# lte_cat_m1_shield_sara-r4.net
KiCad netlist of a schematic drawn in EAGLE
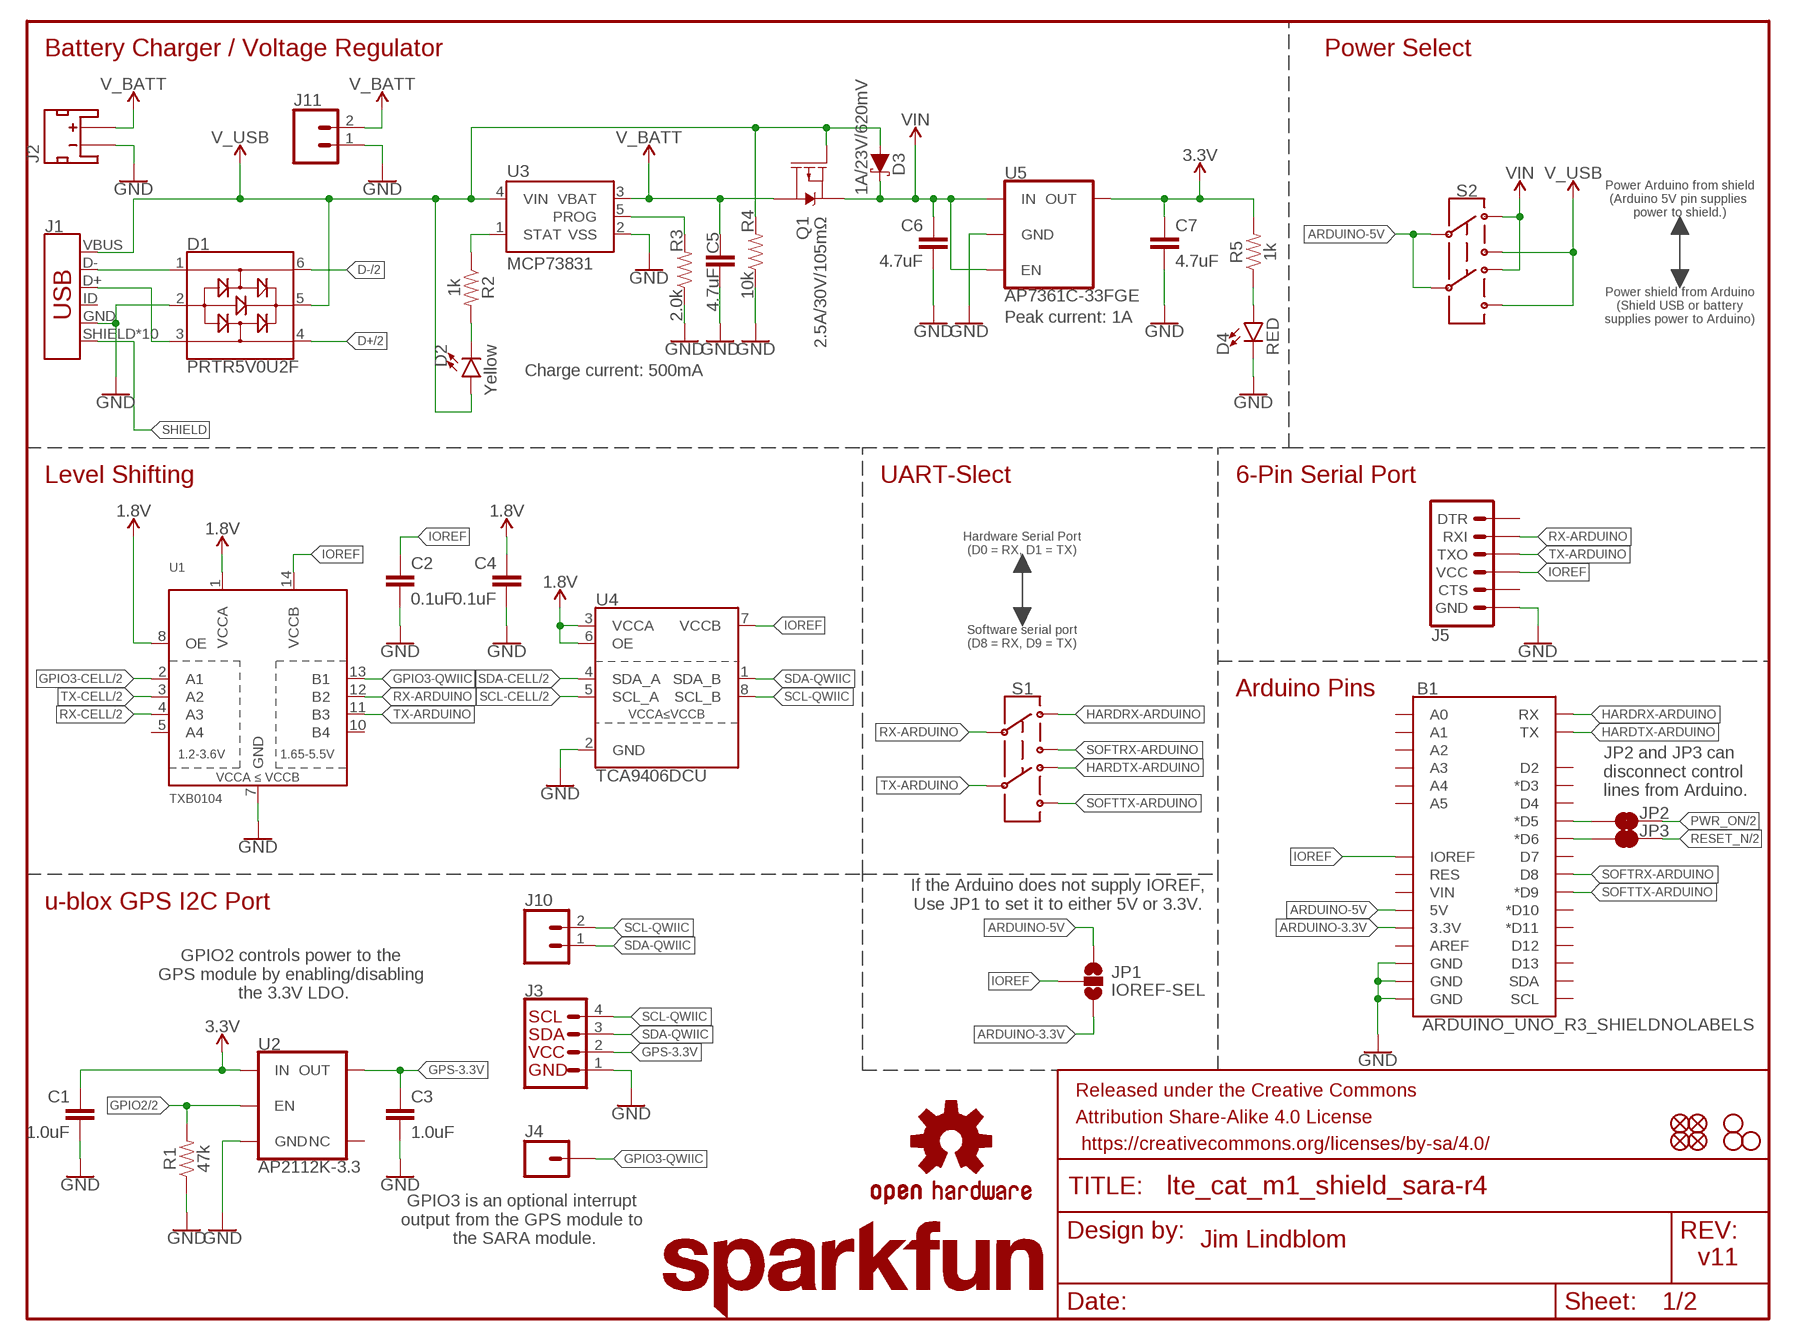
[diagram p0: schematic, sheet 1]
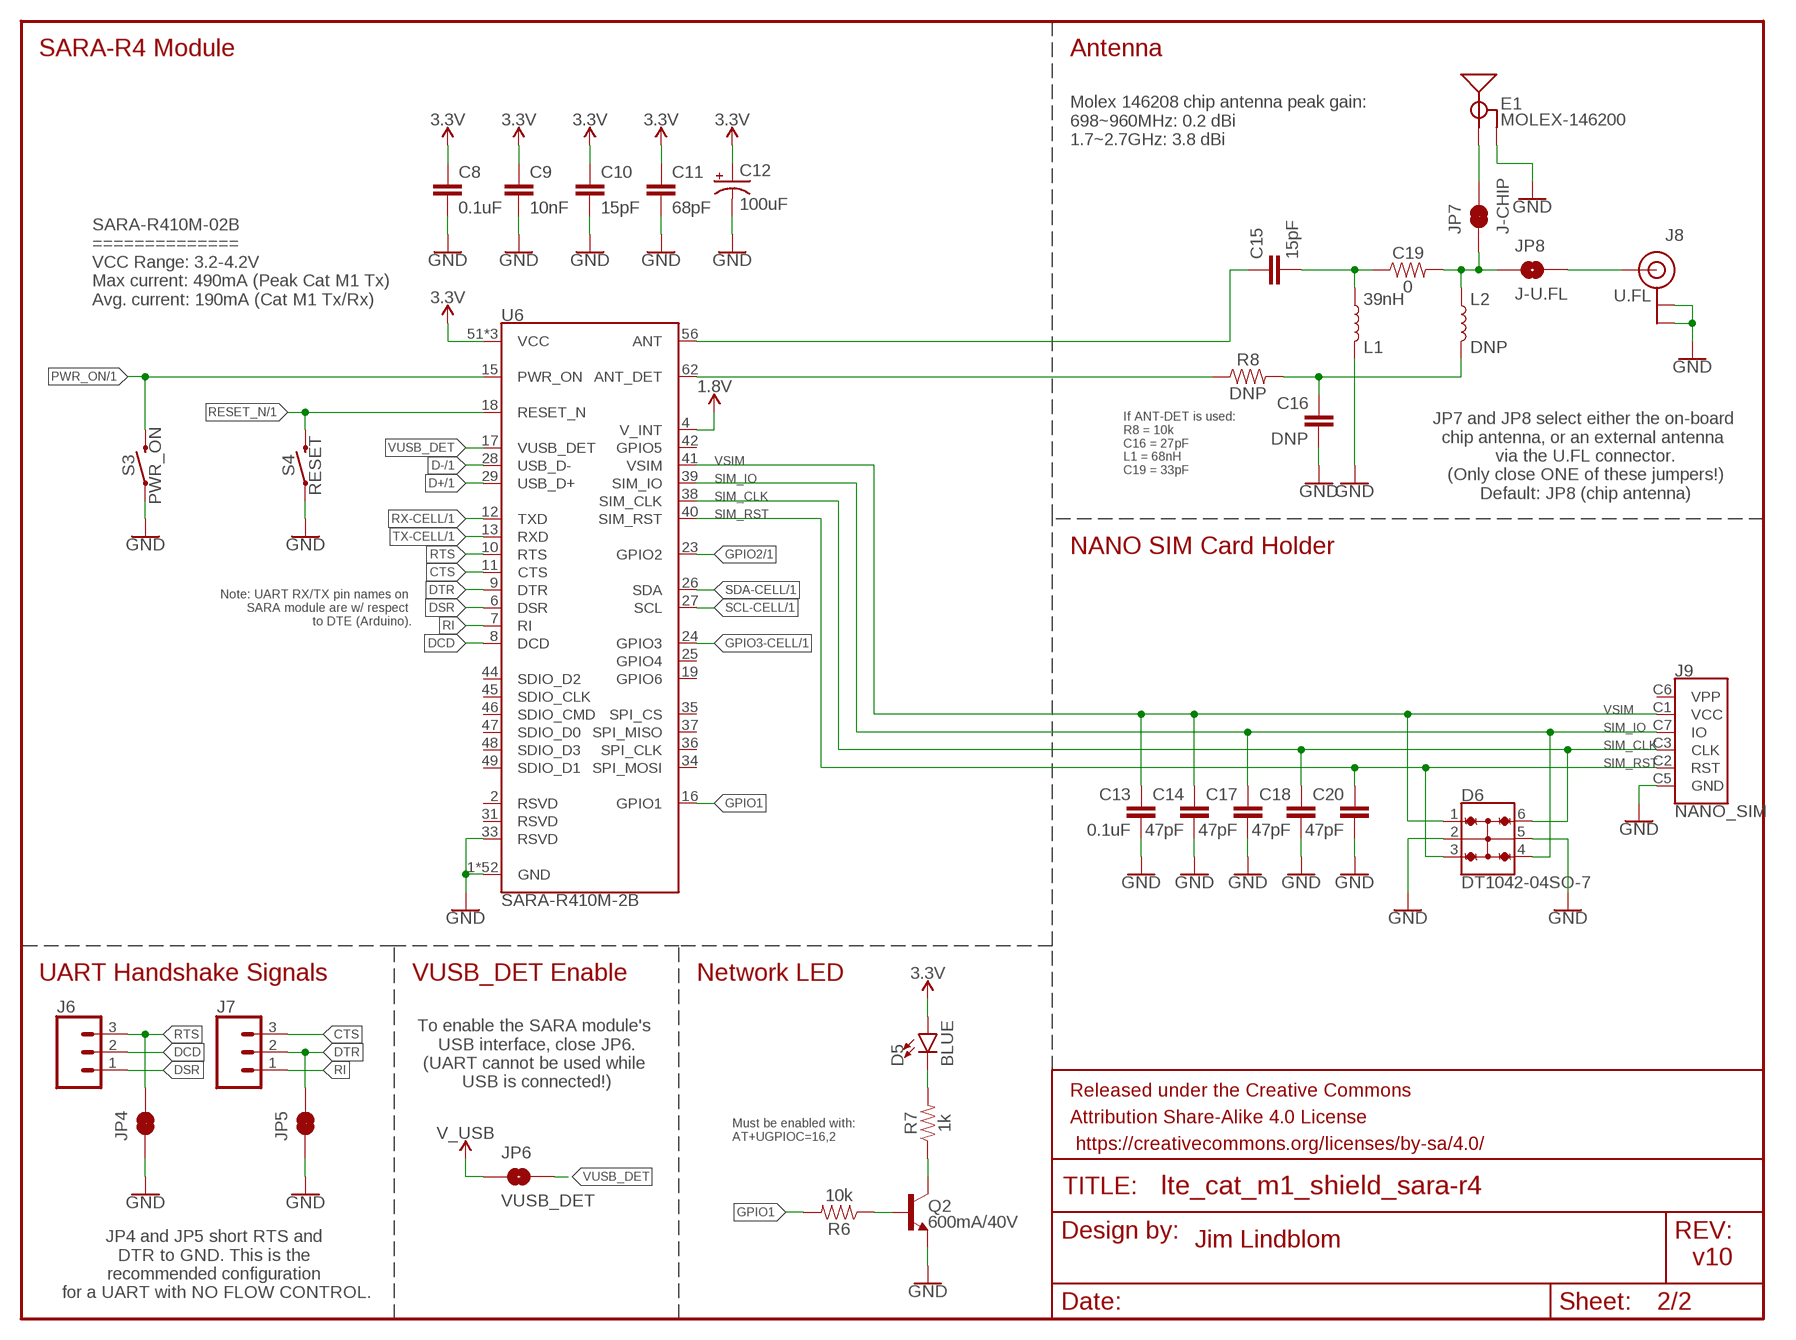
[diagram p1: schematic, sheet 2]

(export (version "E")
  (design (tool "Eeschema 10.0.6"))
  (components
    (comp (ref "B1")
      (value "ARDUINO_UNO_R3_SHIELDNOLABELS")
      (footprint "eagle-import:UNO_R3_SHIELD_NOLABELS")
      (libsource (lib "eagle-import") (part "ARDUINO_UNO_R3_SHIELDNOLABELS"))
    )
    (comp (ref "C1")
      (value "1.0uF")
      (footprint "eagle-import:0603")
      (libsource (lib "eagle-import") (part "1.0UF-0603-16V-10%"))
    )
    (comp (ref "C2")
      (value "0.1uF")
      (footprint "eagle-import:0603")
      (libsource (lib "eagle-import") (part "0.1UF-0603-25V-(+80/-20%)"))
    )
    (comp (ref "C3")
      (value "1.0uF")
      (footprint "eagle-import:0603")
      (libsource (lib "eagle-import") (part "1.0UF-0603-16V-10%"))
    )
    (comp (ref "C4")
      (value "0.1uF")
      (footprint "eagle-import:0603")
      (libsource (lib "eagle-import") (part "0.1UF-0603-25V-(+80/-20%)"))
    )
    (comp (ref "C5")
      (value "4.7uF")
      (footprint "eagle-import:0603")
      (libsource (lib "eagle-import") (part "4.7UF-0603-6.3V-(10%)"))
    )
    (comp (ref "C6")
      (value "4.7uF")
      (footprint "eagle-import:0603")
      (libsource (lib "eagle-import") (part "4.7UF-0603-6.3V-(10%)"))
    )
    (comp (ref "C7")
      (value "4.7uF")
      (footprint "eagle-import:0603")
      (libsource (lib "eagle-import") (part "4.7UF-0603-6.3V-(10%)"))
    )
    (comp (ref "D1")
      (value "PRTR5V0U2F")
      (footprint "eagle-import:SOT886")
      (libsource (lib "eagle-import") (part "PRTR5V0U2F"))
    )
    (comp (ref "D2")
      (value "Yellow")
      (footprint "eagle-import:LED-0603")
      (libsource (lib "eagle-import") (part "LED-YELLOW0603"))
    )
    (comp (ref "D3")
      (value "1A/23V/620mV")
      (footprint "eagle-import:SOD-323")
      (libsource (lib "eagle-import") (part "DIODE-SCHOTTKY-BAT20J"))
    )
    (comp (ref "D4")
      (value "RED")
      (footprint "eagle-import:LED-0603")
      (libsource (lib "eagle-import") (part "LED-RED0603"))
    )
    (comp (ref "FD1")
      (value "FIDUCIALUFIDUCIAL")
      (footprint "eagle-import:FIDUCIAL-MICRO")
      (libsource (lib "eagle-import") (part "FIDUCIALUFIDUCIAL"))
    )
    (comp (ref "FD2")
      (value "FIDUCIALUFIDUCIAL")
      (footprint "eagle-import:FIDUCIAL-MICRO")
      (libsource (lib "eagle-import") (part "FIDUCIALUFIDUCIAL"))
    )
    (comp (ref "FD3")
      (value "FIDUCIALUFIDUCIAL")
      (footprint "eagle-import:FIDUCIAL-MICRO")
      (libsource (lib "eagle-import") (part "FIDUCIALUFIDUCIAL"))
    )
    (comp (ref "FD4")
      (value "FIDUCIALUFIDUCIAL")
      (footprint "eagle-import:FIDUCIAL-MICRO")
      (libsource (lib "eagle-import") (part "FIDUCIALUFIDUCIAL"))
    )
    (comp (ref "FRAME1")
      (value "FRAME-LETTER")
      (footprint "eagle-import:CREATIVE_COMMONS")
      (libsource (lib "eagle-import") (part "FRAME-LETTER"))
    )
    (comp (ref "H1")
      (value "STAND-OFF")
      (footprint "eagle-import:STAND-OFF")
      (libsource (lib "eagle-import") (part "STAND-OFF"))
    )
    (comp (ref "H2")
      (value "STAND-OFF")
      (footprint "eagle-import:STAND-OFF")
      (libsource (lib "eagle-import") (part "STAND-OFF"))
    )
    (comp (ref "H3")
      (value "STAND-OFF")
      (footprint "eagle-import:STAND-OFF")
      (libsource (lib "eagle-import") (part "STAND-OFF"))
    )
    (comp (ref "J1")
      (value "USB_MICRO-B_HALF_PTH_MILL")
      (footprint "eagle-import:USB-MICROB-PTH-MILL")
      (libsource (lib "eagle-import") (part "USB_MICRO-B_HALF_PTH_MILL"))
    )
    (comp (ref "J2")
      (value "JST_2MM_MALESMD")
      (footprint "eagle-import:JST-2-SMD")
      (libsource (lib "eagle-import") (part "JST_2MM_MALESMD"))
    )
    (comp (ref "J3")
      (value "QWIIC_CONNECTORJS-1MM")
      (footprint "eagle-import:1X04_1MM_RA")
      (libsource (lib "eagle-import") (part "QWIIC_CONNECTORJS-1MM"))
    )
    (comp (ref "J4")
      (value "CONN_01PTH_NO_SILK_YES_STOP")
      (footprint "eagle-import:1X01_NO_SILK")
      (libsource (lib "eagle-import") (part "CONN_01PTH_NO_SILK_YES_STOP"))
    )
    (comp (ref "J5")
      (value "6_PIN_SERIAL_TARGETNO_SILK")
      (footprint "eagle-import:1X06_NO_SILK")
      (libsource (lib "eagle-import") (part "6_PIN_SERIAL_TARGETNO_SILK"))
    )
    (comp (ref "J10")
      (value "CONN_021X02_NO_SILK")
      (footprint "eagle-import:1X02_NO_SILK")
      (libsource (lib "eagle-import") (part "CONN_021X02_NO_SILK"))
    )
    (comp (ref "J11")
      (value "CONN_021X02_NO_SILK")
      (footprint "eagle-import:1X02_NO_SILK")
      (libsource (lib "eagle-import") (part "CONN_021X02_NO_SILK"))
    )
    (comp (ref "JP1")
      (value "IOREF-SEL")
      (footprint "eagle-import:SMT-JUMPER_3_NO_SILK")
      (libsource (lib "eagle-import") (part "JUMPER-SMT_3_NO_SILK"))
    )
    (comp (ref "JP2")
      (value "JUMPER-SMT_2_NC_TRACE_SILK")
      (footprint "eagle-import:SMT-JUMPER_2_NC_TRACE_SILK")
      (libsource (lib "eagle-import") (part "JUMPER-SMT_2_NC_TRACE_SILK"))
    )
    (comp (ref "JP3")
      (value "JUMPER-SMT_2_NC_TRACE_SILK")
      (footprint "eagle-import:SMT-JUMPER_2_NC_TRACE_SILK")
      (libsource (lib "eagle-import") (part "JUMPER-SMT_2_NC_TRACE_SILK"))
    )
    (comp (ref "LOGO1")
      (value "SFE_LOGO_NAME.2_INCH")
      (footprint "eagle-import:SFE_LOGO_NAME_.2")
      (libsource (lib "eagle-import") (part "SFE_LOGO_NAME.2_INCH"))
    )
    (comp (ref "LOGO2")
      (value "OSHW-LOGOM")
      (footprint "eagle-import:OSHW-LOGO-M")
      (libsource (lib "eagle-import") (part "OSHW-LOGOM"))
    )
    (comp (ref "LOGO3")
      (value "SFE_LOGO_NAME.2_INCH")
      (footprint "eagle-import:SFE_LOGO_NAME_.2")
      (libsource (lib "eagle-import") (part "SFE_LOGO_NAME.2_INCH"))
    )
    (comp (ref "Q1")
      (value "2.5A/30V/105mΩ")
      (footprint "eagle-import:SOT23-3")
      (libsource (lib "eagle-import") (part "MOSFET_PCH-DMG2307L"))
    )
    (comp (ref "R1")
      (value "47k")
      (footprint "eagle-import:0603")
      (libsource (lib "eagle-import") (part "47KOHM-0603-1/10W-1%"))
    )
    (comp (ref "R2")
      (value "1k")
      (footprint "eagle-import:0603")
      (libsource (lib "eagle-import") (part "1KOHM-0603-1/10W-1%"))
    )
    (comp (ref "R3")
      (value "2.0k")
      (footprint "eagle-import:0603")
      (libsource (lib "eagle-import") (part "2.0KOHM-0603-1/10W-5%"))
    )
    (comp (ref "R4")
      (value "10k")
      (footprint "eagle-import:0603")
      (libsource (lib "eagle-import") (part "10KOHM-0603-1/10W-1%"))
    )
    (comp (ref "R5")
      (value "1k")
      (footprint "eagle-import:0603")
      (libsource (lib "eagle-import") (part "1KOHM-0603-1/10W-1%"))
    )
    (comp (ref "S1")
      (value "SWITCH-DPDT-SMD-AYZ0202")
      (footprint "eagle-import:SWITCH_DPDT_SMD_AYZ0202")
      (libsource (lib "eagle-import") (part "SWITCH-DPDT-SMD-AYZ0202"))
    )
    (comp (ref "S2")
      (value "SWITCH-DPDT-SMD-AYZ0202")
      (footprint "eagle-import:SWITCH_DPDT_SMD_AYZ0202")
      (libsource (lib "eagle-import") (part "SWITCH-DPDT-SMD-AYZ0202"))
    )
    (comp (ref "U1")
      (value "TXB0104")
      (footprint "eagle-import:TSSOP14")
      (libsource (lib "eagle-import") (part "TXB0104PWR"))
    )
    (comp (ref "U2")
      (value "AP2112K-3.3")
      (footprint "eagle-import:SOT23-5")
      (libsource (lib "eagle-import") (part "V_REG_AP2112K-3.3V"))
    )
    (comp (ref "U3")
      (value "MCP73831")
      (footprint "eagle-import:SOT23-5")
      (libsource (lib "eagle-import") (part "MCP73831"))
    )
    (comp (ref "U4")
      (value "TCA9406DCU")
      (footprint "eagle-import:VSSOP-8")
      (libsource (lib "eagle-import") (part "TCA9406DCU"))
    )
    (comp (ref "U5")
      (value "AP7361C-33FGE")
      (footprint "eagle-import:8-UDFN")
      (libsource (lib "eagle-import") (part "AP7361C-33FGE"))
    )
    (comp (ref "C8")
      (value "0.1uF")
      (footprint "eagle-import:0603")
      (libsource (lib "eagle-import") (part "0.1UF-0603-25V-(+80/-20%)"))
    )
    (comp (ref "C9")
      (value "10nF")
      (footprint "eagle-import:0603")
      (libsource (lib "eagle-import") (part "10NF-0603-50V-10%"))
    )
    (comp (ref "C10")
      (value "15pF")
      (footprint "eagle-import:0603")
      (libsource (lib "eagle-import") (part "15PF-0603-50V-5%"))
    )
    (comp (ref "C11")
      (value "68pF")
      (footprint "eagle-import:0603")
      (libsource (lib "eagle-import") (part "68PF-0603-50V-5%"))
    )
    (comp (ref "C12")
      (value "100uF")
      (footprint "eagle-import:1206-POLAR")
      (libsource (lib "eagle-import") (part "100UF-POLAR-1206-6.3V-20%"))
    )
    (comp (ref "C13")
      (value "0.1uF")
      (footprint "eagle-import:0603")
      (libsource (lib "eagle-import") (part "0.1UF-0603-25V-(+80/-20%)"))
    )
    (comp (ref "C14")
      (value "47pF")
      (footprint "eagle-import:0603")
      (libsource (lib "eagle-import") (part "47PF-0603-50V-5%"))
    )
    (comp (ref "C15")
      (value "15pF")
      (footprint "eagle-import:0603")
      (libsource (lib "eagle-import") (part "15PF-0603-50V-5%"))
    )
    (comp (ref "C16")
      (value "DNP")
      (footprint "eagle-import:0603")
      (libsource (lib "eagle-import") (part "27PF-0603-50V-5%"))
    )
    (comp (ref "C17")
      (value "47pF")
      (footprint "eagle-import:0603")
      (libsource (lib "eagle-import") (part "47PF-0603-50V-5%"))
    )
    (comp (ref "C18")
      (value "47pF")
      (footprint "eagle-import:0603")
      (libsource (lib "eagle-import") (part "47PF-0603-50V-5%"))
    )
    (comp (ref "C19")
      (value "0")
      (footprint "eagle-import:0603")
      (libsource (lib "eagle-import") (part "0OHM-0603-1/10W-5%"))
    )
    (comp (ref "C20")
      (value "47pF")
      (footprint "eagle-import:0603")
      (libsource (lib "eagle-import") (part "47PF-0603-50V-5%"))
    )
    (comp (ref "D5")
      (value "BLUE")
      (footprint "eagle-import:LED-0603")
      (libsource (lib "eagle-import") (part "LED-BLUE0603"))
    )
    (comp (ref "D6")
      (value "DT1042-04SO-7")
      (footprint "eagle-import:SOT23-6L")
      (libsource (lib "eagle-import") (part "TVS_DIODE_ARRAY_4DT1042-04SO-7"))
    )
    (comp (ref "E1")
      (value "MOLEX-146200")
      (footprint "eagle-import:MOLEX_146200")
      (libsource (lib "eagle-import") (part "ANTENNA-GROUNDEDMOLEX-146200"))
    )
    (comp (ref "FRAME2")
      (value "FRAME-LETTER")
      (footprint "eagle-import:CREATIVE_COMMONS")
      (libsource (lib "eagle-import") (part "FRAME-LETTER"))
    )
    (comp (ref "J6")
      (value "CONN_031X03_NO_SILK")
      (footprint "eagle-import:1X03_NO_SILK")
      (libsource (lib "eagle-import") (part "CONN_031X03_NO_SILK"))
    )
    (comp (ref "J7")
      (value "CONN_031X03_NO_SILK")
      (footprint "eagle-import:1X03_NO_SILK")
      (libsource (lib "eagle-import") (part "CONN_031X03_NO_SILK"))
    )
    (comp (ref "J8")
      (value "U.FL")
      (footprint "eagle-import:U.FL")
      (libsource (lib "eagle-import") (part "U.FL"))
    )
    (comp (ref "J9")
      (value "NANO_SIM")
      (footprint "eagle-import:NANO_SIM_WURTH_693043020611")
      (libsource (lib "eagle-import") (part "NANO_SIMWURTH"))
    )
    (comp (ref "JP4")
      (value "JUMPER-SMT_2_NC_TRACE_SILK")
      (footprint "eagle-import:SMT-JUMPER_2_NC_TRACE_SILK")
      (libsource (lib "eagle-import") (part "JUMPER-SMT_2_NC_TRACE_SILK"))
    )
    (comp (ref "JP5")
      (value "JUMPER-SMT_2_NC_TRACE_SILK")
      (footprint "eagle-import:SMT-JUMPER_2_NC_TRACE_SILK")
      (libsource (lib "eagle-import") (part "JUMPER-SMT_2_NC_TRACE_SILK"))
    )
    (comp (ref "JP6")
      (value "VUSB_DET")
      (footprint "eagle-import:SMT-JUMPER_2_NO_SILK")
      (libsource (lib "eagle-import") (part "JUMPER-SMT_2_NO_SILK"))
    )
    (comp (ref "JP7")
      (value "J-CHIP")
      (footprint "eagle-import:SMT-JUMPER_2_NC_TRACE_NO-SILK")
      (libsource (lib "eagle-import") (part "JUMPER-SMT_2_NC_TRACE_NO-SILK"))
    )
    (comp (ref "JP8")
      (value "J-U.FL")
      (footprint "eagle-import:SMT-JUMPER_2_NO_NO-SILK")
      (libsource (lib "eagle-import") (part "JUMPER-SMT_2_NO_NO-SILK"))
    )
    (comp (ref "L1")
      (value "39nH")
      (footprint "eagle-import:0603")
      (libsource (lib "eagle-import") (part "INDUCTOR-0603-39NH"))
    )
    (comp (ref "L2")
      (value "DNP")
      (footprint "eagle-import:0603")
      (libsource (lib "eagle-import") (part "INDUCTOR-0603-68NH"))
    )
    (comp (ref "Q2")
      (value "600mA/40V")
      (footprint "eagle-import:SOT23-3")
      (libsource (lib "eagle-import") (part "TRANS_NPN-MMBT2222AL"))
    )
    (comp (ref "R6")
      (value "10k")
      (footprint "eagle-import:0603")
      (libsource (lib "eagle-import") (part "10KOHM-0603-1/10W-1%"))
    )
    (comp (ref "R7")
      (value "1k")
      (footprint "eagle-import:0603")
      (libsource (lib "eagle-import") (part "1KOHM-0603-1/10W-1%"))
    )
    (comp (ref "R8")
      (value "DNP")
      (footprint "eagle-import:0603")
      (libsource (lib "eagle-import") (part "10KOHM-0603-1/10W-1%"))
    )
    (comp (ref "S3")
      (value "PWR_ON")
      (footprint "eagle-import:TACTILE_SWITCH_SMD_5.2MM")
      (libsource (lib "eagle-import") (part "MOMENTARY-SWITCH-SPST-SMD-5.2-REDUNDANT"))
    )
    (comp (ref "S4")
      (value "RESET")
      (footprint "eagle-import:TACTILE_SWITCH_SMD_5.2MM")
      (libsource (lib "eagle-import") (part "MOMENTARY-SWITCH-SPST-SMD-5.2-REDUNDANT"))
    )
    (comp (ref "U6")
      (value "SARA-R410M-2B")
      (footprint "eagle-import:SARA-LGA")
      (libsource (lib "eagle-import") (part "SARA-R4"))
    )
  )
  (nets
    (net (code "1") (name "1.8V") (class "Default")
      (node (ref "C4") (pin "1") (pinfunction "1_1") (pintype "passive"))
      (node (ref "U1") (pin "1") (pinfunction "VCCA_1") (pintype "bidirectional"))
      (node (ref "U1") (pin "8") (pinfunction "OE_8") (pintype "bidirectional"))
      (node (ref "U4") (pin "3") (pinfunction "VCCA_3") (pintype "bidirectional"))
      (node (ref "U4") (pin "6") (pinfunction "OE_6") (pintype "bidirectional"))
      (node (ref "U6") (pin "4") (pinfunction "V_INT_4") (pintype "bidirectional"))
    )
    (net (code "2") (name "3.3V") (class "Default")
      (node (ref "C1") (pin "1") (pinfunction "1_1") (pintype "passive"))
      (node (ref "C10") (pin "1") (pinfunction "1_1") (pintype "passive"))
      (node (ref "C11") (pin "1") (pinfunction "1_1") (pintype "passive"))
      (node (ref "C12") (pin "1") (pinfunction "+_1") (pintype "passive"))
      (node (ref "C7") (pin "1") (pinfunction "1_1") (pintype "passive"))
      (node (ref "C8") (pin "1") (pinfunction "1_1") (pintype "passive"))
      (node (ref "C9") (pin "1") (pinfunction "1_1") (pintype "passive"))
      (node (ref "D5") (pin "A") (pinfunction "A_A") (pintype "passive"))
      (node (ref "R5") (pin "2") (pinfunction "2_2") (pintype "passive"))
      (node (ref "U2") (pin "1") (pinfunction "IN_1") (pintype "input"))
      (node (ref "U5") (pin "1") (pinfunction "OUT_1") (pintype "output"))
      (node (ref "U6") (pin "51") (pinfunction "VCC_51") (pintype "bidirectional"))
      (node (ref "U6") (pin "52") (pinfunction "VCC_52") (pintype "bidirectional"))
      (node (ref "U6") (pin "53") (pinfunction "VCC_53") (pintype "bidirectional"))
    )
    (net (code "3") (name "ARDUINO-3.3V") (class "Default")
      (node (ref "B1") (pin "3.3V") (pinfunction "3.3V_3.3V") (pintype "bidirectional"))
      (node (ref "JP1") (pin "3") (pinfunction "3_3") (pintype "passive"))
    )
    (net (code "4") (name "ARDUINO-5V") (class "Default")
      (node (ref "B1") (pin "5V") (pinfunction "5V_5V") (pintype "bidirectional"))
      (node (ref "JP1") (pin "1") (pinfunction "1_1") (pintype "passive"))
      (node (ref "S2") (pin "2") (pinfunction "2_2") (pintype "bidirectional"))
      (node (ref "S2") (pin "5") (pinfunction "5_5") (pintype "bidirectional"))
    )
    (net (code "5") (name "CTS") (class "Default")
      (node (ref "J7") (pin "3") (pinfunction "3_3") (pintype "passive"))
      (node (ref "U6") (pin "11") (pinfunction "CTS_11") (pintype "bidirectional"))
    )
    (net (code "6") (name "D+") (class "Default")
      (node (ref "D1") (pin "4") (pinfunction "4_4") (pintype "bidirectional"))
      (node (ref "U6") (pin "29") (pinfunction "USB_D+_29") (pintype "bidirectional"))
    )
    (net (code "7") (name "D-") (class "Default")
      (node (ref "D1") (pin "6") (pinfunction "6_6") (pintype "bidirectional"))
      (node (ref "U6") (pin "28") (pinfunction "USB_D-_28") (pintype "bidirectional"))
    )
    (net (code "8") (name "DCD") (class "Default")
      (node (ref "J6") (pin "2") (pinfunction "2_2") (pintype "passive"))
      (node (ref "U6") (pin "8") (pinfunction "DCD_8") (pintype "bidirectional"))
    )
    (net (code "9") (name "DSR") (class "Default")
      (node (ref "J6") (pin "1") (pinfunction "1_1") (pintype "passive"))
      (node (ref "U6") (pin "6") (pinfunction "DSR_6") (pintype "bidirectional"))
    )
    (net (code "10") (name "DTR") (class "Default")
      (node (ref "J7") (pin "2") (pinfunction "2_2") (pintype "passive"))
      (node (ref "JP5") (pin "2") (pinfunction "2_2") (pintype "passive"))
      (node (ref "U6") (pin "9") (pinfunction "DTR_9") (pintype "bidirectional"))
    )
    (net (code "11") (name "GND") (class "Default")
      (node (ref "B1") (pin "GND@0") (pinfunction "GND_GND@0") (pintype "bidirectional"))
      (node (ref "B1") (pin "GND@1") (pinfunction "GND_GND@1") (pintype "bidirectional"))
      (node (ref "B1") (pin "GND@2") (pinfunction "GND_GND@2") (pintype "bidirectional"))
      (node (ref "C1") (pin "2") (pinfunction "2_2") (pintype "passive"))
      (node (ref "C10") (pin "2") (pinfunction "2_2") (pintype "passive"))
      (node (ref "C11") (pin "2") (pinfunction "2_2") (pintype "passive"))
      (node (ref "C12") (pin "2") (pinfunction "-_2") (pintype "passive"))
      (node (ref "C13") (pin "2") (pinfunction "2_2") (pintype "passive"))
      (node (ref "C14") (pin "2") (pinfunction "2_2") (pintype "passive"))
      (node (ref "C16") (pin "2") (pinfunction "2_2") (pintype "passive"))
      (node (ref "C17") (pin "2") (pinfunction "2_2") (pintype "passive"))
      (node (ref "C18") (pin "2") (pinfunction "2_2") (pintype "passive"))
      (node (ref "C2") (pin "2") (pinfunction "2_2") (pintype "passive"))
      (node (ref "C20") (pin "2") (pinfunction "2_2") (pintype "passive"))
      (node (ref "C3") (pin "2") (pinfunction "2_2") (pintype "passive"))
      (node (ref "C4") (pin "2") (pinfunction "2_2") (pintype "passive"))
      (node (ref "C5") (pin "2") (pinfunction "2_2") (pintype "passive"))
      (node (ref "C6") (pin "2") (pinfunction "2_2") (pintype "passive"))
      (node (ref "C7") (pin "2") (pinfunction "2_2") (pintype "passive"))
      (node (ref "C8") (pin "2") (pinfunction "2_2") (pintype "passive"))
      (node (ref "C9") (pin "2") (pinfunction "2_2") (pintype "passive"))
      (node (ref "D1") (pin "2") (pinfunction "2_2") (pintype "bidirectional"))
      (node (ref "D4") (pin "C") (pinfunction "C_C") (pintype "passive"))
      (node (ref "D6") (pin "2") (pinfunction "2_2") (pintype "bidirectional"))
      (node (ref "D6") (pin "5") (pinfunction "5_5") (pintype "bidirectional"))
      (node (ref "E1") (pin "GND") (pinfunction "GND_GND") (pintype "bidirectional"))
      (node (ref "J1") (pin "GND") (pinfunction "GND_GND") (pintype "power_in"))
      (node (ref "J11") (pin "1") (pinfunction "1_1") (pintype "passive"))
      (node (ref "J2") (pin "1") (pinfunction "-_1") (pintype "bidirectional"))
      (node (ref "J3") (pin "1") (pinfunction "1_1") (pintype "power_in"))
      (node (ref "J5") (pin "6") (pinfunction "GND_6") (pintype "passive"))
      (node (ref "J8") (pin "1") (pinfunction "GND_1") (pintype "bidirectional"))
      (node (ref "J8") (pin "2") (pinfunction "GND_2") (pintype "bidirectional"))
      (node (ref "J9") (pin "C5") (pinfunction "GND_C5") (pintype "bidirectional"))
      (node (ref "JP4") (pin "1") (pinfunction "1_1") (pintype "passive"))
      (node (ref "JP5") (pin "1") (pinfunction "1_1") (pintype "passive"))
      (node (ref "L1") (pin "1") (pinfunction "1_1") (pintype "passive"))
      (node (ref "Q2") (pin "2") (pinfunction "E_2") (pintype "passive"))
      (node (ref "R1") (pin "1") (pinfunction "1_1") (pintype "passive"))
      (node (ref "R3") (pin "1") (pinfunction "1_1") (pintype "passive"))
      (node (ref "R4") (pin "1") (pinfunction "1_1") (pintype "passive"))
      (node (ref "S3") (pin "1") (pinfunction "1_1") (pintype "passive"))
      (node (ref "S3") (pin "2") (pinfunction "1_2") (pintype "passive"))
      (node (ref "S4") (pin "1") (pinfunction "1_1") (pintype "passive"))
      (node (ref "S4") (pin "2") (pinfunction "1_2") (pintype "passive"))
      (node (ref "U1") (pin "7") (pinfunction "GND_7") (pintype "bidirectional"))
      (node (ref "U2") (pin "2") (pinfunction "GND_2") (pintype "input"))
      (node (ref "U3") (pin "2") (pinfunction "VSS_2") (pintype "power_in"))
      (node (ref "U4") (pin "2") (pinfunction "GND_2") (pintype "bidirectional"))
      (node (ref "U5") (pin "4") (pinfunction "GND_4") (pintype "input"))
      (node (ref "U5") (pin "EP") (pinfunction "GND_EP") (pintype "input"))
      (node (ref "U6") (pin "1") (pinfunction "GND_1") (pintype "bidirectional"))
      (node (ref "U6") (pin "14") (pinfunction "GND_14") (pintype "bidirectional"))
      (node (ref "U6") (pin "20") (pinfunction "GND_20") (pintype "bidirectional"))
      (node (ref "U6") (pin "21") (pinfunction "GND_21") (pintype "bidirectional"))
      (node (ref "U6") (pin "22") (pinfunction "GND_22") (pintype "bidirectional"))
      (node (ref "U6") (pin "3") (pinfunction "GND_3") (pintype "bidirectional"))
      (node (ref "U6") (pin "30") (pinfunction "GND_30") (pintype "bidirectional"))
      (node (ref "U6") (pin "32") (pinfunction "GND_32") (pintype "bidirectional"))
      (node (ref "U6") (pin "33") (pinfunction "RSVD_33") (pintype "bidirectional"))
      (node (ref "U6") (pin "43") (pinfunction "GND_43") (pintype "bidirectional"))
      (node (ref "U6") (pin "5") (pinfunction "GND_5") (pintype "bidirectional"))
      (node (ref "U6") (pin "50") (pinfunction "GND_50") (pintype "bidirectional"))
      (node (ref "U6") (pin "54") (pinfunction "GND_54") (pintype "bidirectional"))
      (node (ref "U6") (pin "55") (pinfunction "GND_55") (pintype "bidirectional"))
      (node (ref "U6") (pin "57") (pinfunction "GND_57") (pintype "bidirectional"))
      (node (ref "U6") (pin "58") (pinfunction "GND_58") (pintype "bidirectional"))
      (node (ref "U6") (pin "59") (pinfunction "GND_59") (pintype "bidirectional"))
      (node (ref "U6") (pin "60") (pinfunction "GND_60") (pintype "bidirectional"))
      (node (ref "U6") (pin "61") (pinfunction "GND_61") (pintype "bidirectional"))
      (node (ref "U6") (pin "63") (pinfunction "GND_63") (pintype "bidirectional"))
      (node (ref "U6") (pin "64") (pinfunction "GND_64") (pintype "bidirectional"))
      (node (ref "U6") (pin "65") (pinfunction "GND_65") (pintype "bidirectional"))
      (node (ref "U6") (pin "66") (pinfunction "GND_66") (pintype "bidirectional"))
      (node (ref "U6") (pin "67") (pinfunction "GND_67") (pintype "bidirectional"))
      (node (ref "U6") (pin "68") (pinfunction "GND_68") (pintype "bidirectional"))
      (node (ref "U6") (pin "69") (pinfunction "GND_69") (pintype "bidirectional"))
      (node (ref "U6") (pin "70") (pinfunction "GND_70") (pintype "bidirectional"))
      (node (ref "U6") (pin "71") (pinfunction "GND_71") (pintype "bidirectional"))
      (node (ref "U6") (pin "72") (pinfunction "GND_72") (pintype "bidirectional"))
      (node (ref "U6") (pin "73") (pinfunction "GND_73") (pintype "bidirectional"))
      (node (ref "U6") (pin "74") (pinfunction "GND_74") (pintype "bidirectional"))
      (node (ref "U6") (pin "75") (pinfunction "GND_75") (pintype "bidirectional"))
      (node (ref "U6") (pin "76") (pinfunction "GND_76") (pintype "bidirectional"))
      (node (ref "U6") (pin "77") (pinfunction "GND_77") (pintype "bidirectional"))
      (node (ref "U6") (pin "78") (pinfunction "GND_78") (pintype "bidirectional"))
      (node (ref "U6") (pin "79") (pinfunction "GND_79") (pintype "bidirectional"))
      (node (ref "U6") (pin "80") (pinfunction "GND_80") (pintype "bidirectional"))
      (node (ref "U6") (pin "81") (pinfunction "GND_81") (pintype "bidirectional"))
      (node (ref "U6") (pin "82") (pinfunction "GND_82") (pintype "bidirectional"))
      (node (ref "U6") (pin "83") (pinfunction "GND_83") (pintype "bidirectional"))
      (node (ref "U6") (pin "84") (pinfunction "GND_84") (pintype "bidirectional"))
      (node (ref "U6") (pin "85") (pinfunction "GND_85") (pintype "bidirectional"))
      (node (ref "U6") (pin "86") (pinfunction "GND_86") (pintype "bidirectional"))
      (node (ref "U6") (pin "87") (pinfunction "GND_87") (pintype "bidirectional"))
      (node (ref "U6") (pin "88") (pinfunction "GND_88") (pintype "bidirectional"))
      (node (ref "U6") (pin "89") (pinfunction "GND_89") (pintype "bidirectional"))
      (node (ref "U6") (pin "90") (pinfunction "GND_90") (pintype "bidirectional"))
      (node (ref "U6") (pin "91") (pinfunction "GND_91") (pintype "bidirectional"))
      (node (ref "U6") (pin "92") (pinfunction "GND_92") (pintype "bidirectional"))
      (node (ref "U6") (pin "93") (pinfunction "GND_93") (pintype "bidirectional"))
      (node (ref "U6") (pin "94") (pinfunction "GND_94") (pintype "bidirectional"))
      (node (ref "U6") (pin "95") (pinfunction "GND_95") (pintype "bidirectional"))
      (node (ref "U6") (pin "96") (pinfunction "GND_96") (pintype "bidirectional"))
    )
    (net (code "12") (name "GPIO1") (class "Default")
      (node (ref "R6") (pin "2") (pinfunction "2_2") (pintype "passive"))
      (node (ref "U6") (pin "16") (pinfunction "GPIO1_16") (pintype "bidirectional"))
    )
    (net (code "13") (name "GPIO2") (class "Default")
      (node (ref "R1") (pin "2") (pinfunction "2_2") (pintype "passive"))
      (node (ref "U2") (pin "3") (pinfunction "EN_3") (pintype "input"))
      (node (ref "U6") (pin "23") (pinfunction "GPIO2_23") (pintype "bidirectional"))
    )
    (net (code "14") (name "GPIO3-CELL") (class "Default")
      (node (ref "U1") (pin "2") (pinfunction "A1_2") (pintype "bidirectional"))
      (node (ref "U6") (pin "24") (pinfunction "GPIO3_24") (pintype "bidirectional"))
    )
    (net (code "15") (name "GPIO3-QWIIC") (class "Default")
      (node (ref "J4") (pin "1") (pinfunction "1_1") (pintype "passive"))
      (node (ref "U1") (pin "13") (pinfunction "B1_13") (pintype "bidirectional"))
    )
    (net (code "16") (name "GPS-3.3V") (class "Default")
      (node (ref "C3") (pin "1") (pinfunction "1_1") (pintype "passive"))
      (node (ref "J3") (pin "2") (pinfunction "2_2") (pintype "power_in"))
      (node (ref "U2") (pin "5") (pinfunction "OUT_5") (pintype "passive"))
    )
    (net (code "17") (name "HARDRX-ARDUINO") (class "Default")
      (node (ref "B1") (pin "RX") (pinfunction "RX_RX") (pintype "bidirectional"))
      (node (ref "S1") (pin "1") (pinfunction "1_1") (pintype "bidirectional"))
    )
    (net (code "18") (name "HARDTX-ARDUINO") (class "Default")
      (node (ref "B1") (pin "TX") (pinfunction "TX_TX") (pintype "bidirectional"))
      (node (ref "S1") (pin "4") (pinfunction "4_4") (pintype "bidirectional"))
    )
    (net (code "19") (name "IOREF") (class "Default")
      (node (ref "B1") (pin "IOREF") (pinfunction "IOREF_IOREF") (pintype "bidirectional"))
      (node (ref "C2") (pin "1") (pinfunction "1_1") (pintype "passive"))
      (node (ref "J5") (pin "4") (pinfunction "VCC_4") (pintype "passive"))
      (node (ref "JP1") (pin "2") (pinfunction "2_2") (pintype "passive"))
      (node (ref "U1") (pin "14") (pinfunction "VCCB_14") (pintype "bidirectional"))
      (node (ref "U4") (pin "7") (pinfunction "VCCB_7") (pintype "bidirectional"))
    )
    (net (code "20") (name "Net-(B1-*D5)") (class "Default")
      (node (ref "B1") (pin "D5") (pinfunction "*D5_D5") (pintype "bidirectional"))
      (node (ref "JP2") (pin "1") (pinfunction "1_1") (pintype "passive"))
    )
    (net (code "21") (name "Net-(B1-*D6)") (class "Default")
      (node (ref "B1") (pin "D6") (pinfunction "*D6_D6") (pintype "bidirectional"))
      (node (ref "JP3") (pin "1") (pinfunction "1_1") (pintype "passive"))
    )
    (net (code "22") (name "Net-(C15-Pad2)") (class "Default")
      (node (ref "C15") (pin "2") (pinfunction "2_2") (pintype "passive"))
      (node (ref "C19") (pin "1") (pinfunction "1_1") (pintype "passive"))
      (node (ref "L1") (pin "2") (pinfunction "2_2") (pintype "passive"))
    )
    (net (code "23") (name "Net-(C16-Pad1)") (class "Default")
      (node (ref "C16") (pin "1") (pinfunction "1_1") (pintype "passive"))
      (node (ref "L2") (pin "2") (pinfunction "2_2") (pintype "passive"))
      (node (ref "R8") (pin "2") (pinfunction "2_2") (pintype "passive"))
    )
    (net (code "24") (name "Net-(C19-Pad2)") (class "Default")
      (node (ref "C19") (pin "2") (pinfunction "2_2") (pintype "passive"))
      (node (ref "JP7") (pin "1") (pinfunction "1_1") (pintype "passive"))
      (node (ref "JP8") (pin "1") (pinfunction "1_1") (pintype "passive"))
      (node (ref "L2") (pin "1") (pinfunction "1_1") (pintype "passive"))
    )
    (net (code "25") (name "Net-(D1-Pad1)") (class "Default")
      (node (ref "D1") (pin "1") (pinfunction "1_1") (pintype "bidirectional"))
      (node (ref "J1") (pin "D-") (pinfunction "D-_D-") (pintype "bidirectional"))
    )
    (net (code "26") (name "Net-(D1-Pad3)") (class "Default")
      (node (ref "D1") (pin "3") (pinfunction "3_3") (pintype "bidirectional"))
      (node (ref "J1") (pin "D+") (pinfunction "D+_D+") (pintype "bidirectional"))
    )
    (net (code "27") (name "Net-(D2-PadC)") (class "Default")
      (node (ref "D2") (pin "C") (pinfunction "C_C") (pintype "passive"))
      (node (ref "R2") (pin "2") (pinfunction "2_2") (pintype "passive"))
    )
    (net (code "28") (name "Net-(D4-PadA)") (class "Default")
      (node (ref "D4") (pin "A") (pinfunction "A_A") (pintype "passive"))
      (node (ref "R5") (pin "1") (pinfunction "1_1") (pintype "passive"))
    )
    (net (code "29") (name "Net-(D5-PadC)") (class "Default")
      (node (ref "D5") (pin "C") (pinfunction "C_C") (pintype "passive"))
      (node (ref "R7") (pin "2") (pinfunction "2_2") (pintype "passive"))
    )
    (net (code "30") (name "Net-(E1-SIGNAL)") (class "Default")
      (node (ref "E1") (pin "FEED") (pinfunction "SIGNAL_FEED") (pintype "bidirectional"))
      (node (ref "JP7") (pin "2") (pinfunction "2_2") (pintype "passive"))
    )
    (net (code "31") (name "Net-(J8-SIGNAL)") (class "Default")
      (node (ref "J8") (pin "FEED") (pinfunction "SIGNAL_FEED") (pintype "bidirectional"))
      (node (ref "JP8") (pin "2") (pinfunction "2_2") (pintype "passive"))
    )
    (net (code "32") (name "Net-(Q2-B)") (class "Default")
      (node (ref "Q2") (pin "1") (pinfunction "B_1") (pintype "passive"))
      (node (ref "R6") (pin "1") (pinfunction "1_1") (pintype "passive"))
    )
    (net (code "33") (name "Net-(Q2-C)") (class "Default")
      (node (ref "Q2") (pin "3") (pinfunction "C_3") (pintype "passive"))
      (node (ref "R7") (pin "1") (pinfunction "1_1") (pintype "passive"))
    )
    (net (code "34") (name "Net-(U3-PROG)") (class "Default")
      (node (ref "R3") (pin "2") (pinfunction "2_2") (pintype "passive"))
      (node (ref "U3") (pin "5") (pinfunction "PROG_5") (pintype "input"))
    )
    (net (code "35") (name "Net-(U3-STAT)") (class "Default")
      (node (ref "R2") (pin "1") (pinfunction "1_1") (pintype "passive"))
      (node (ref "U3") (pin "1") (pinfunction "STAT_1") (pintype "output"))
    )
    (net (code "36") (name "Net-(U6-ANT)") (class "Default")
      (node (ref "C15") (pin "1") (pinfunction "1_1") (pintype "passive"))
      (node (ref "U6") (pin "56") (pinfunction "ANT_56") (pintype "bidirectional"))
    )
    (net (code "37") (name "Net-(U6-ANT_DET)") (class "Default")
      (node (ref "R8") (pin "1") (pinfunction "1_1") (pintype "passive"))
      (node (ref "U6") (pin "62") (pinfunction "ANT_DET_62") (pintype "bidirectional"))
    )
    (net (code "38") (name "PWR_ON") (class "Default")
      (node (ref "JP2") (pin "2") (pinfunction "2_2") (pintype "passive"))
      (node (ref "S3") (pin "3") (pinfunction "2_3") (pintype "passive"))
      (node (ref "S3") (pin "4") (pinfunction "2_4") (pintype "passive"))
      (node (ref "U6") (pin "15") (pinfunction "PWR_ON_15") (pintype "bidirectional"))
    )
    (net (code "39") (name "RESET_N") (class "Default")
      (node (ref "JP3") (pin "2") (pinfunction "2_2") (pintype "passive"))
      (node (ref "S4") (pin "3") (pinfunction "2_3") (pintype "passive"))
      (node (ref "S4") (pin "4") (pinfunction "2_4") (pintype "passive"))
      (node (ref "U6") (pin "18") (pinfunction "RESET_N_18") (pintype "bidirectional"))
    )
    (net (code "40") (name "RI") (class "Default")
      (node (ref "J7") (pin "1") (pinfunction "1_1") (pintype "passive"))
      (node (ref "U6") (pin "7") (pinfunction "RI_7") (pintype "bidirectional"))
    )
    (net (code "41") (name "RTS") (class "Default")
      (node (ref "J6") (pin "3") (pinfunction "3_3") (pintype "passive"))
      (node (ref "JP4") (pin "2") (pinfunction "2_2") (pintype "passive"))
      (node (ref "U6") (pin "10") (pinfunction "RTS_10") (pintype "bidirectional"))
    )
    (net (code "42") (name "RX-ARDUINO") (class "Default")
      (node (ref "J5") (pin "2") (pinfunction "RXI_2") (pintype "passive"))
      (node (ref "S1") (pin "2") (pinfunction "2_2") (pintype "bidirectional"))
      (node (ref "U1") (pin "12") (pinfunction "B2_12") (pintype "bidirectional"))
    )
    (net (code "43") (name "RX-CELL") (class "Default")
      (node (ref "U1") (pin "4") (pinfunction "A3_4") (pintype "bidirectional"))
      (node (ref "U6") (pin "12") (pinfunction "TXD_12") (pintype "bidirectional"))
    )
    (net (code "44") (name "SCL-CELL") (class "Default")
      (node (ref "U4") (pin "5") (pinfunction "SCL_A_5") (pintype "bidirectional"))
      (node (ref "U6") (pin "27") (pinfunction "SCL_27") (pintype "bidirectional"))
    )
    (net (code "45") (name "SCL-QWIIC") (class "Default")
      (node (ref "J10") (pin "2") (pinfunction "2_2") (pintype "passive"))
      (node (ref "J3") (pin "4") (pinfunction "4_4") (pintype "passive"))
      (node (ref "U4") (pin "8") (pinfunction "SCL_B_8") (pintype "bidirectional"))
    )
    (net (code "46") (name "SDA-CELL") (class "Default")
      (node (ref "U4") (pin "4") (pinfunction "SDA_A_4") (pintype "bidirectional"))
      (node (ref "U6") (pin "26") (pinfunction "SDA_26") (pintype "bidirectional"))
    )
    (net (code "47") (name "SDA-QWIIC") (class "Default")
      (node (ref "J10") (pin "1") (pinfunction "1_1") (pintype "passive"))
      (node (ref "J3") (pin "3") (pinfunction "3_3") (pintype "passive"))
      (node (ref "U4") (pin "1") (pinfunction "SDA_B_1") (pintype "bidirectional"))
    )
    (net (code "48") (name "SHIELD") (class "Default")
      (node (ref "J1") (pin "SHIELD") (pinfunction "SHIELD_SHIELD") (pintype "bidirectional"))
      (node (ref "J1") (pin "SHIELD10") (pinfunction "SHIELD_SHIELD10") (pintype "bidirectional"))
      (node (ref "J1") (pin "SHIELD2") (pinfunction "SHIELD_SHIELD2") (pintype "bidirectional"))
      (node (ref "J1") (pin "SHIELD3") (pinfunction "SHIELD_SHIELD3") (pintype "bidirectional"))
      (node (ref "J1") (pin "SHIELD4") (pinfunction "SHIELD_SHIELD4") (pintype "bidirectional"))
      (node (ref "J1") (pin "SHIELD5") (pinfunction "SHIELD_SHIELD5") (pintype "bidirectional"))
      (node (ref "J1") (pin "SHIELD6") (pinfunction "SHIELD_SHIELD6") (pintype "bidirectional"))
      (node (ref "J1") (pin "SHIELD7") (pinfunction "SHIELD_SHIELD7") (pintype "bidirectional"))
      (node (ref "J1") (pin "SHIELD8") (pinfunction "SHIELD_SHIELD8") (pintype "bidirectional"))
      (node (ref "J1") (pin "SHIELD9") (pinfunction "SHIELD_SHIELD9") (pintype "bidirectional"))
    )
    (net (code "49") (name "SIM_CLK") (class "Default")
      (node (ref "C18") (pin "1") (pinfunction "1_1") (pintype "passive"))
      (node (ref "D6") (pin "6") (pinfunction "6_6") (pintype "bidirectional"))
      (node (ref "J9") (pin "C3") (pinfunction "CLK_C3") (pintype "bidirectional"))
      (node (ref "U6") (pin "38") (pinfunction "SIM_CLK_38") (pintype "bidirectional"))
    )
    (net (code "50") (name "SIM_IO") (class "Default")
      (node (ref "C17") (pin "1") (pinfunction "1_1") (pintype "passive"))
      (node (ref "D6") (pin "4") (pinfunction "4_4") (pintype "bidirectional"))
      (node (ref "J9") (pin "C7") (pinfunction "IO_C7") (pintype "bidirectional"))
      (node (ref "U6") (pin "39") (pinfunction "SIM_IO_39") (pintype "bidirectional"))
    )
    (net (code "51") (name "SIM_RST") (class "Default")
      (node (ref "C20") (pin "1") (pinfunction "1_1") (pintype "passive"))
      (node (ref "D6") (pin "3") (pinfunction "3_3") (pintype "bidirectional"))
      (node (ref "J9") (pin "C2") (pinfunction "RST_C2") (pintype "bidirectional"))
      (node (ref "U6") (pin "40") (pinfunction "SIM_RST_40") (pintype "bidirectional"))
    )
    (net (code "52") (name "SOFTRX-ARDUINO") (class "Default")
      (node (ref "B1") (pin "D8") (pinfunction "D8_D8") (pintype "bidirectional"))
      (node (ref "S1") (pin "3") (pinfunction "3_3") (pintype "bidirectional"))
    )
    (net (code "53") (name "SOFTTX-ARDUINO") (class "Default")
      (node (ref "B1") (pin "D9") (pinfunction "*D9_D9") (pintype "bidirectional"))
      (node (ref "S1") (pin "6") (pinfunction "6_6") (pintype "bidirectional"))
    )
    (net (code "54") (name "TX-ARDUINO") (class "Default")
      (node (ref "J5") (pin "3") (pinfunction "TXO_3") (pintype "passive"))
      (node (ref "S1") (pin "5") (pinfunction "5_5") (pintype "bidirectional"))
      (node (ref "U1") (pin "11") (pinfunction "B3_11") (pintype "bidirectional"))
    )
    (net (code "55") (name "TX-CELL") (class "Default")
      (node (ref "U1") (pin "3") (pinfunction "A2_3") (pintype "bidirectional"))
      (node (ref "U6") (pin "13") (pinfunction "RXD_13") (pintype "bidirectional"))
    )
    (net (code "56") (name "VIN") (class "Default")
      (node (ref "C6") (pin "1") (pinfunction "1_1") (pintype "passive"))
      (node (ref "D3") (pin "C") (pinfunction "C_C") (pintype "passive"))
      (node (ref "Q1") (pin "2") (pinfunction "S_2") (pintype "bidirectional"))
      (node (ref "S2") (pin "1") (pinfunction "1_1") (pintype "bidirectional"))
      (node (ref "S2") (pin "4") (pinfunction "4_4") (pintype "bidirectional"))
      (node (ref "U5") (pin "5") (pinfunction "EN_5") (pintype "bidirectional"))
      (node (ref "U5") (pin "8") (pinfunction "IN_8") (pintype "input"))
    )
    (net (code "57") (name "VSIM") (class "Default")
      (node (ref "C13") (pin "1") (pinfunction "1_1") (pintype "passive"))
      (node (ref "C14") (pin "1") (pinfunction "1_1") (pintype "passive"))
      (node (ref "D6") (pin "1") (pinfunction "1_1") (pintype "bidirectional"))
      (node (ref "J9") (pin "C1") (pinfunction "VCC_C1") (pintype "bidirectional"))
      (node (ref "U6") (pin "41") (pinfunction "VSIM_41") (pintype "bidirectional"))
    )
    (net (code "58") (name "VUSB_DET") (class "Default")
      (node (ref "JP6") (pin "2") (pinfunction "2_2") (pintype "passive"))
      (node (ref "U6") (pin "17") (pinfunction "VUSB_DET_17") (pintype "bidirectional"))
    )
    (net (code "59") (name "V_BATT") (class "Default")
      (node (ref "C5") (pin "1") (pinfunction "1_1") (pintype "passive"))
      (node (ref "J11") (pin "2") (pinfunction "2_2") (pintype "passive"))
      (node (ref "J2") (pin "2") (pinfunction "+_2") (pintype "bidirectional"))
      (node (ref "Q1") (pin "3") (pinfunction "D_3") (pintype "bidirectional"))
      (node (ref "U3") (pin "3") (pinfunction "VBAT_3") (pintype "power_in"))
    )
    (net (code "60") (name "V_USB") (class "Default")
      (node (ref "D1") (pin "5") (pinfunction "5_5") (pintype "bidirectional"))
      (node (ref "D2") (pin "A") (pinfunction "A_A") (pintype "passive"))
      (node (ref "D3") (pin "A") (pinfunction "A_A") (pintype "passive"))
      (node (ref "J1") (pin "VBUS") (pinfunction "VBUS_VBUS") (pintype "power_in"))
      (node (ref "JP6") (pin "1") (pinfunction "1_1") (pintype "passive"))
      (node (ref "Q1") (pin "1") (pinfunction "G_1") (pintype "bidirectional"))
      (node (ref "R4") (pin "2") (pinfunction "2_2") (pintype "passive"))
      (node (ref "S2") (pin "3") (pinfunction "3_3") (pintype "bidirectional"))
      (node (ref "S2") (pin "6") (pinfunction "6_6") (pintype "bidirectional"))
      (node (ref "U3") (pin "4") (pinfunction "VIN_4") (pintype "power_in"))
    )
    (net (code "61") (name "unconnected-(B1-*D3-PadD3)") (class "Default")
      (node (ref "B1") (pin "D3") (pinfunction "*D3_D3") (pintype "bidirectional"))
    )
    (net (code "62") (name "unconnected-(B1-*D10-PadD10)") (class "Default")
      (node (ref "B1") (pin "D10") (pinfunction "*D10_D10") (pintype "bidirectional"))
    )
    (net (code "63") (name "unconnected-(B1-*D11-PadD11)") (class "Default")
      (node (ref "B1") (pin "D11") (pinfunction "*D11_D11") (pintype "bidirectional"))
    )
    (net (code "64") (name "unconnected-(B1-PadA0)") (class "Default")
      (node (ref "B1") (pin "A0") (pinfunction "A0_A0") (pintype "bidirectional"))
    )
    (net (code "65") (name "unconnected-(B1-PadA1)") (class "Default")
      (node (ref "B1") (pin "A1") (pinfunction "A1_A1") (pintype "bidirectional"))
    )
    (net (code "66") (name "unconnected-(B1-PadA2)") (class "Default")
      (node (ref "B1") (pin "A2") (pinfunction "A2_A2") (pintype "bidirectional"))
    )
    (net (code "67") (name "unconnected-(B1-PadA3)") (class "Default")
      (node (ref "B1") (pin "A3") (pinfunction "A3_A3") (pintype "bidirectional"))
    )
    (net (code "68") (name "unconnected-(B1-PadA4)") (class "Default")
      (node (ref "B1") (pin "A4") (pinfunction "A4_A4") (pintype "bidirectional"))
    )
    (net (code "69") (name "unconnected-(B1-PadA5)") (class "Default")
      (node (ref "B1") (pin "A5") (pinfunction "A5_A5") (pintype "bidirectional"))
    )
    (net (code "70") (name "unconnected-(B1-PadAREF)") (class "Default")
      (node (ref "B1") (pin "AREF") (pinfunction "AREF_AREF") (pintype "bidirectional"))
    )
    (net (code "71") (name "unconnected-(B1-PadD2)") (class "Default")
      (node (ref "B1") (pin "D2") (pinfunction "D2_D2") (pintype "bidirectional"))
    )
    (net (code "72") (name "unconnected-(B1-PadD4)") (class "Default")
      (node (ref "B1") (pin "D4") (pinfunction "D4_D4") (pintype "bidirectional"))
    )
    (net (code "73") (name "unconnected-(B1-PadD7)") (class "Default")
      (node (ref "B1") (pin "D7") (pinfunction "D7_D7") (pintype "bidirectional"))
    )
    (net (code "74") (name "unconnected-(B1-PadD12)") (class "Default")
      (node (ref "B1") (pin "D12") (pinfunction "D12_D12") (pintype "bidirectional"))
    )
    (net (code "75") (name "unconnected-(B1-PadD13)") (class "Default")
      (node (ref "B1") (pin "D13") (pinfunction "D13_D13") (pintype "bidirectional"))
    )
    (net (code "76") (name "unconnected-(B1-PadRES)") (class "Default")
      (node (ref "B1") (pin "RES") (pinfunction "RES_RES") (pintype "bidirectional"))
    )
    (net (code "77") (name "unconnected-(B1-PadSCL)") (class "Default")
      (node (ref "B1") (pin "SCL") (pinfunction "SCL_SCL") (pintype "bidirectional"))
    )
    (net (code "78") (name "unconnected-(B1-PadSDA)") (class "Default")
      (node (ref "B1") (pin "SDA") (pinfunction "SDA_SDA") (pintype "bidirectional"))
    )
    (net (code "79") (name "unconnected-(B1-PadVIN)") (class "Default")
      (node (ref "B1") (pin "VIN") (pinfunction "VIN_VIN") (pintype "bidirectional"))
    )
    (net (code "80") (name "unconnected-(J1-PadID)") (class "Default")
      (node (ref "J1") (pin "ID") (pinfunction "ID_ID") (pintype "bidirectional"))
    )
    (net (code "81") (name "unconnected-(J5-CTS-Pad5)") (class "Default")
      (node (ref "J5") (pin "5") (pinfunction "CTS_5") (pintype "passive"))
    )
    (net (code "82") (name "unconnected-(J5-DTR-Pad1)") (class "Default")
      (node (ref "J5") (pin "1") (pinfunction "DTR_1") (pintype "passive"))
    )
    (net (code "83") (name "unconnected-(J9-VPP-PadC6)") (class "Default")
      (node (ref "J9") (pin "C6") (pinfunction "VPP_C6") (pintype "bidirectional"))
    )
    (net (code "84") (name "unconnected-(U1-A4-Pad5)") (class "Default")
      (node (ref "U1") (pin "5") (pinfunction "A4_5") (pintype "bidirectional"))
    )
    (net (code "85") (name "unconnected-(U1-B4-Pad10)") (class "Default")
      (node (ref "U1") (pin "10") (pinfunction "B4_10") (pintype "bidirectional"))
    )
    (net (code "86") (name "unconnected-(U2-NC-Pad4)") (class "Default")
      (node (ref "U2") (pin "4") (pinfunction "NC_4") (pintype "no_connect"))
    )
    (net (code "87") (name "unconnected-(U6-GPIO4-Pad25)") (class "Default")
      (node (ref "U6") (pin "25") (pinfunction "GPIO4_25") (pintype "bidirectional"))
    )
    (net (code "88") (name "unconnected-(U6-GPIO5-Pad42)") (class "Default")
      (node (ref "U6") (pin "42") (pinfunction "GPIO5_42") (pintype "bidirectional"))
    )
    (net (code "89") (name "unconnected-(U6-GPIO6-Pad19)") (class "Default")
      (node (ref "U6") (pin "19") (pinfunction "GPIO6_19") (pintype "bidirectional"))
    )
    (net (code "90") (name "unconnected-(U6-RSVD-Pad2)") (class "Default")
      (node (ref "U6") (pin "2") (pinfunction "RSVD_2") (pintype "bidirectional"))
    )
    (net (code "91") (name "unconnected-(U6-RSVD-Pad31)") (class "Default")
      (node (ref "U6") (pin "31") (pinfunction "RSVD_31") (pintype "bidirectional"))
    )
    (net (code "92") (name "unconnected-(U6-SDIO_CLK-Pad45)") (class "Default")
      (node (ref "U6") (pin "45") (pinfunction "SDIO_CLK_45") (pintype "bidirectional"))
    )
    (net (code "93") (name "unconnected-(U6-SDIO_CMD-Pad46)") (class "Default")
      (node (ref "U6") (pin "46") (pinfunction "SDIO_CMD_46") (pintype "bidirectional"))
    )
    (net (code "94") (name "unconnected-(U6-SDIO_D0-Pad47)") (class "Default")
      (node (ref "U6") (pin "47") (pinfunction "SDIO_D0_47") (pintype "bidirectional"))
    )
    (net (code "95") (name "unconnected-(U6-SDIO_D1-Pad49)") (class "Default")
      (node (ref "U6") (pin "49") (pinfunction "SDIO_D1_49") (pintype "bidirectional"))
    )
    (net (code "96") (name "unconnected-(U6-SDIO_D2-Pad44)") (class "Default")
      (node (ref "U6") (pin "44") (pinfunction "SDIO_D2_44") (pintype "bidirectional"))
    )
    (net (code "97") (name "unconnected-(U6-SDIO_D3-Pad48)") (class "Default")
      (node (ref "U6") (pin "48") (pinfunction "SDIO_D3_48") (pintype "bidirectional"))
    )
    (net (code "98") (name "unconnected-(U6-SPI_CLK-Pad36)") (class "Default")
      (node (ref "U6") (pin "36") (pinfunction "SPI_CLK_36") (pintype "bidirectional"))
    )
    (net (code "99") (name "unconnected-(U6-SPI_CS-Pad35)") (class "Default")
      (node (ref "U6") (pin "35") (pinfunction "SPI_CS_35") (pintype "bidirectional"))
    )
    (net (code "100") (name "unconnected-(U6-SPI_MISO-Pad37)") (class "Default")
      (node (ref "U6") (pin "37") (pinfunction "SPI_MISO_37") (pintype "bidirectional"))
    )
    (net (code "101") (name "unconnected-(U6-SPI_MOSI-Pad34)") (class "Default")
      (node (ref "U6") (pin "34") (pinfunction "SPI_MOSI_34") (pintype "bidirectional"))
    )
  )
)
